# VSCard_v3_1.net
KiCad netlist of a schematic drawn in EAGLE
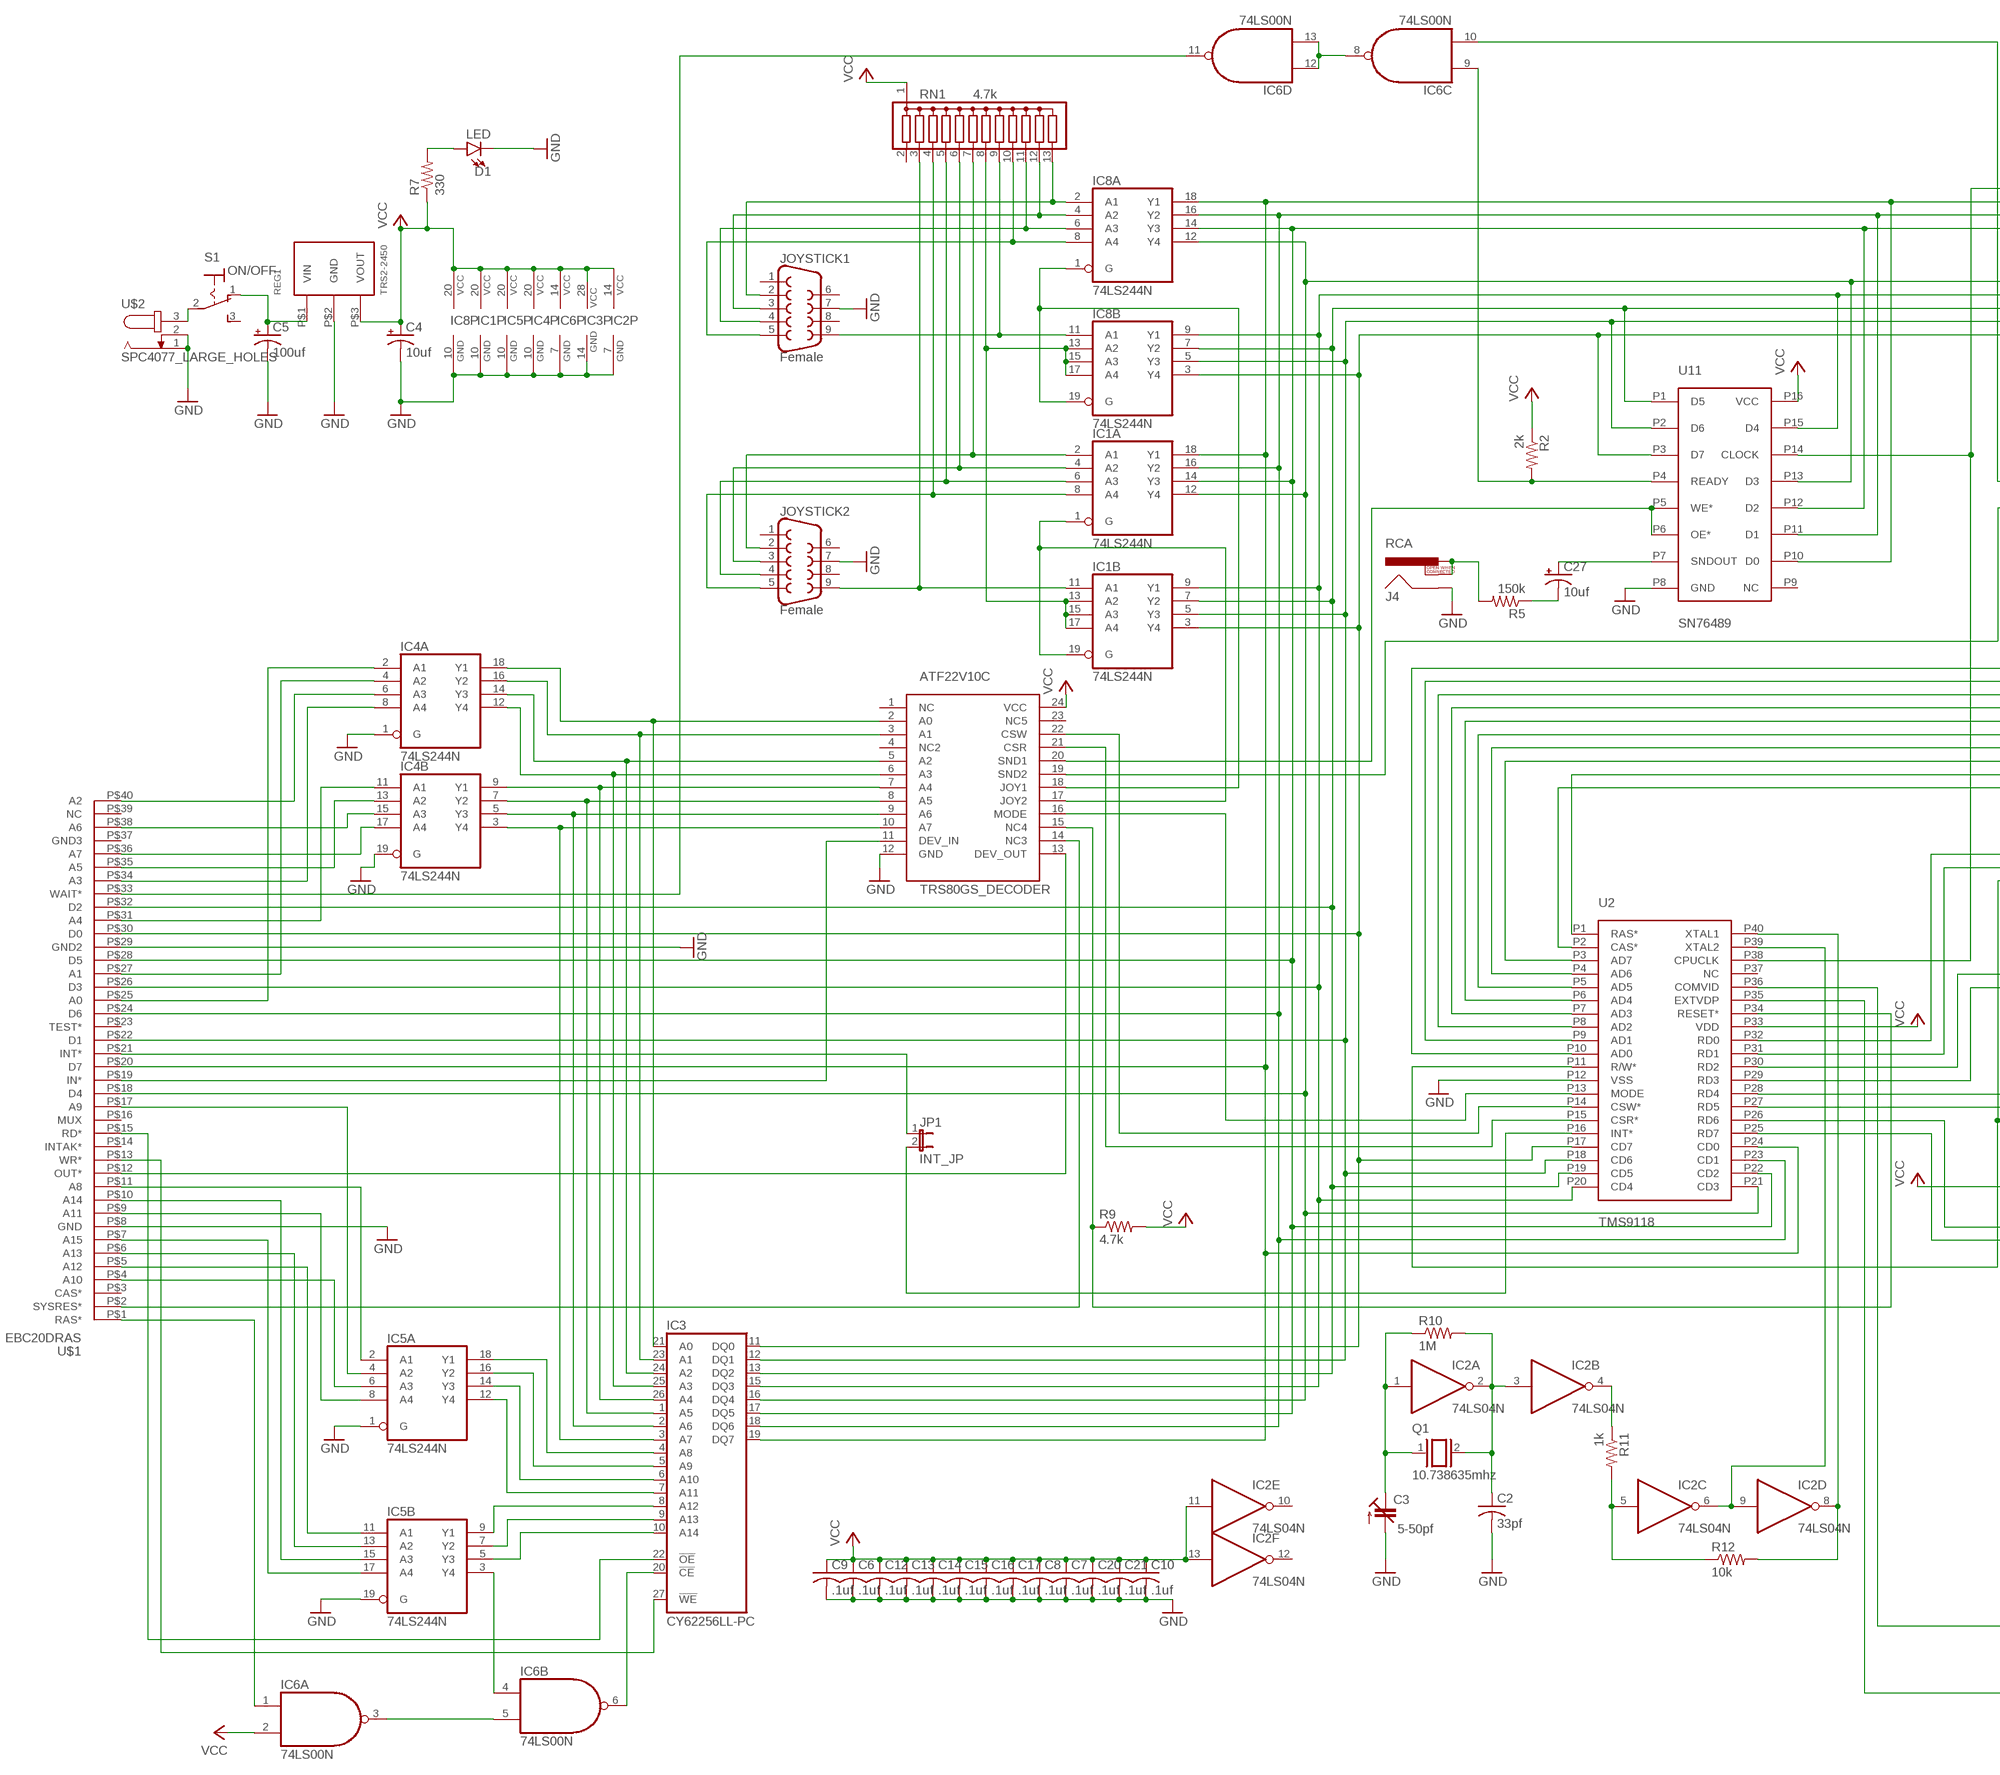
[diagram p0: schematic, sheet 1, part 1 of 2]
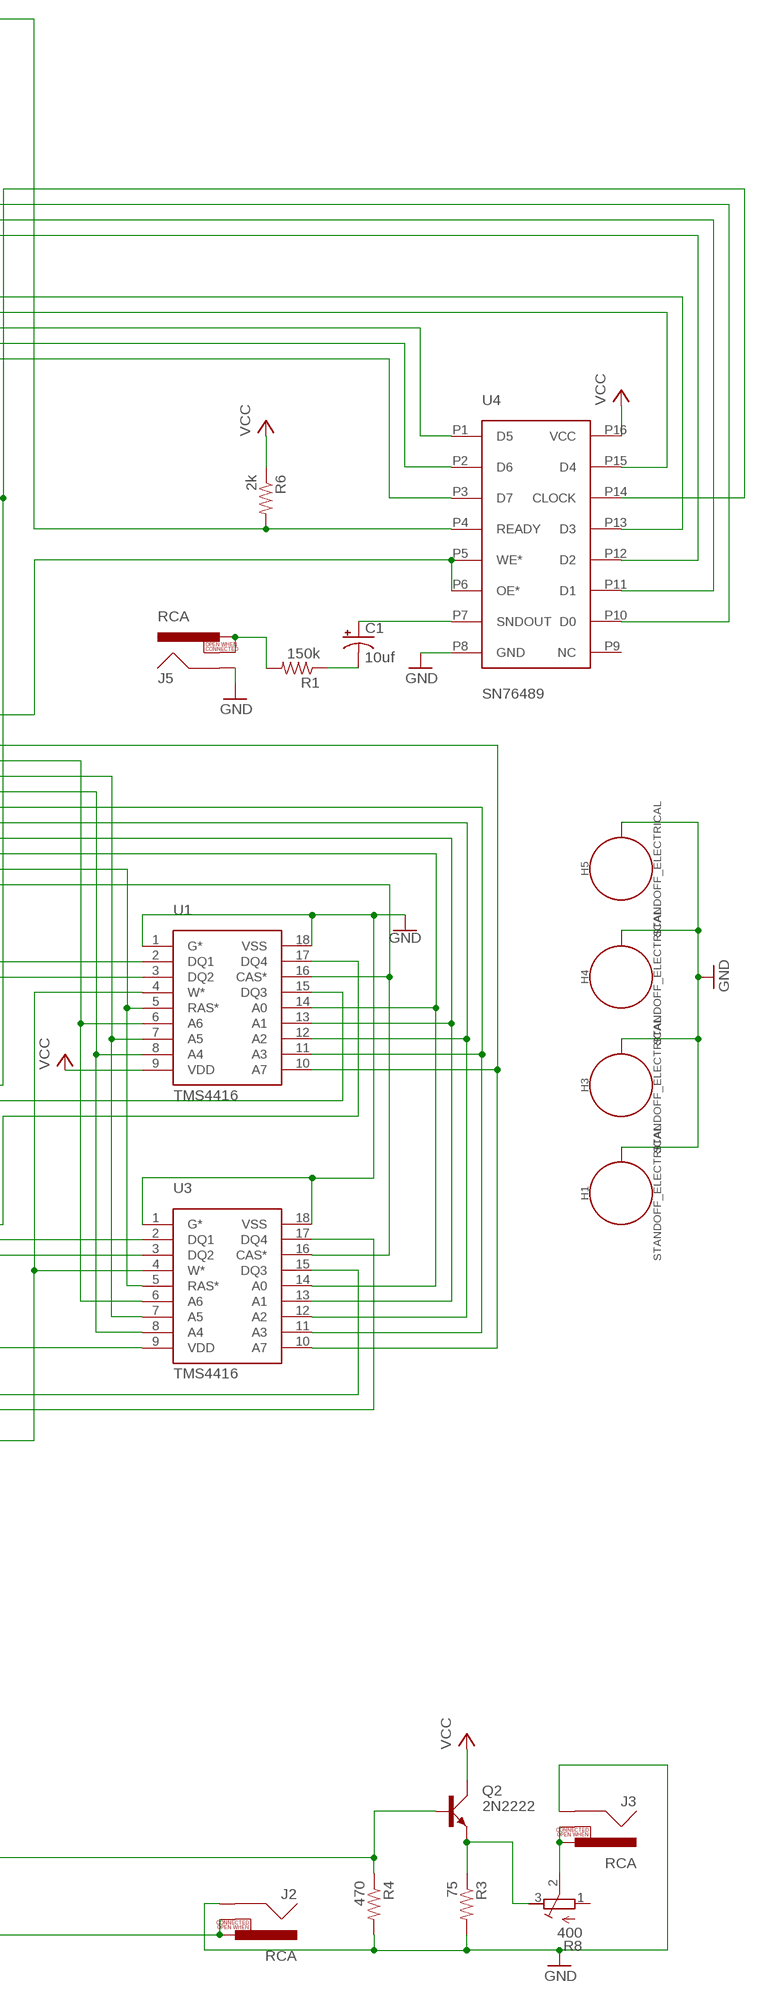
[diagram p1: schematic, sheet 1, part 2 of 2]

(export (version "E")
  (design (tool "Eeschema 10.0.6"))
  (components
    (comp (ref "ATF22V10C")
      (value "TRS80GS_DECODER")
      (footprint "eagle-import:DIP24SKI")
      (libsource (lib "eagle-import") (part "TRS80GS_DECODER"))
    )
    (comp (ref "C1")
      (value "10uf")
      (footprint "eagle-import:E2,5-6")
      (libsource (lib "eagle-import") (part "resistor_348_CPOL-USE2.5-6"))
    )
    (comp (ref "C2")
      (value "33pf")
      (footprint "eagle-import:C050-025X075")
      (libsource (lib "eagle-import") (part "C-US050-025X075"))
    )
    (comp (ref "C3")
      (value "5-50pf")
      (footprint "eagle-import:CTRIM3050.504")
      (libsource (lib "eagle-import") (part "C-TRIMM3050.504"))
    )
    (comp (ref "C4")
      (value "10uf")
      (footprint "eagle-import:E2,5-5")
      (libsource (lib "eagle-import") (part "resistor_348_CPOL-USE2.5-5"))
    )
    (comp (ref "C5")
      (value "100uf")
      (footprint "eagle-import:E3,5-10")
      (libsource (lib "eagle-import") (part "CPOL-USE3.5-10"))
    )
    (comp (ref "C6")
      (value ".1uf")
      (footprint "eagle-import:C025-025X050")
      (libsource (lib "eagle-import") (part "resistor_348_C-US025-025X050"))
    )
    (comp (ref "C7")
      (value ".1uf")
      (footprint "eagle-import:C025-025X050")
      (libsource (lib "eagle-import") (part "resistor_348_C-US025-025X050"))
    )
    (comp (ref "C8")
      (value ".1uf")
      (footprint "eagle-import:C025-025X050")
      (libsource (lib "eagle-import") (part "resistor_348_C-US025-025X050"))
    )
    (comp (ref "C9")
      (value ".1uf")
      (footprint "eagle-import:C025-025X050")
      (libsource (lib "eagle-import") (part "resistor_348_C-US025-025X050"))
    )
    (comp (ref "C10")
      (value ".1uf")
      (footprint "eagle-import:C025-025X050")
      (libsource (lib "eagle-import") (part "resistor_348_C-US025-025X050"))
    )
    (comp (ref "C12")
      (value ".1uf")
      (footprint "eagle-import:C025-025X050")
      (libsource (lib "eagle-import") (part "resistor_348_C-US025-025X050"))
    )
    (comp (ref "C13")
      (value ".1uf")
      (footprint "eagle-import:C025-025X050")
      (libsource (lib "eagle-import") (part "resistor_348_C-US025-025X050"))
    )
    (comp (ref "C14")
      (value ".1uf")
      (footprint "eagle-import:C025-025X050")
      (libsource (lib "eagle-import") (part "resistor_348_C-US025-025X050"))
    )
    (comp (ref "C15")
      (value ".1uf")
      (footprint "eagle-import:C025-025X050")
      (libsource (lib "eagle-import") (part "resistor_348_C-US025-025X050"))
    )
    (comp (ref "C16")
      (value ".1uf")
      (footprint "eagle-import:C025-025X050")
      (libsource (lib "eagle-import") (part "resistor_348_C-US025-025X050"))
    )
    (comp (ref "C17")
      (value ".1uf")
      (footprint "eagle-import:C025-025X050")
      (libsource (lib "eagle-import") (part "resistor_348_C-US025-025X050"))
    )
    (comp (ref "C20")
      (value ".1uf")
      (footprint "eagle-import:C025-025X050")
      (libsource (lib "eagle-import") (part "resistor_348_C-US025-025X050"))
    )
    (comp (ref "C21")
      (value ".1uf")
      (footprint "eagle-import:C025-025X050")
      (libsource (lib "eagle-import") (part "resistor_348_C-US025-025X050"))
    )
    (comp (ref "C27")
      (value "10uf")
      (footprint "eagle-import:E2,5-6")
      (libsource (lib "eagle-import") (part "resistor_348_CPOL-USE2.5-6"))
    )
    (comp (ref "D1")
      (value "LED")
      (footprint "eagle-import:LED_3MM")
      (libsource (lib "eagle-import") (part "LED3MM"))
    )
    (comp (ref "H1")
      (value "STANDOFF_ELECTRICAL")
      (footprint "eagle-import:STANDOFF-ELECTRICAL")
      (libsource (lib "eagle-import") (part "STANDOFF_ELECTRICAL"))
    )
    (comp (ref "H3")
      (value "STANDOFF_ELECTRICAL")
      (footprint "eagle-import:STANDOFF-ELECTRICAL")
      (libsource (lib "eagle-import") (part "STANDOFF_ELECTRICAL"))
    )
    (comp (ref "H4")
      (value "STANDOFF_ELECTRICAL")
      (footprint "eagle-import:STANDOFF-ELECTRICAL")
      (libsource (lib "eagle-import") (part "STANDOFF_ELECTRICAL"))
    )
    (comp (ref "H5")
      (value "STANDOFF_ELECTRICAL")
      (footprint "eagle-import:STANDOFF-ELECTRICAL")
      (libsource (lib "eagle-import") (part "STANDOFF_ELECTRICAL"))
    )
    (comp (ref "IC1")
      (value "74LS244N")
      (footprint "eagle-import:DIL20")
      (libsource (lib "eagle-import") (part "74244NLS"))
    )
    (comp (ref "IC2")
      (value "74LS04N")
      (footprint "eagle-import:DIL14")
      (libsource (lib "eagle-import") (part "7404NLS"))
    )
    (comp (ref "IC3")
      (value "CY62256LL-PC")
      (footprint "eagle-import:DIL28-6")
      (libsource (lib "eagle-import") (part "CY62256LL-?PC"))
    )
    (comp (ref "IC4")
      (value "74LS244N")
      (footprint "eagle-import:DIL20")
      (libsource (lib "eagle-import") (part "74244NLS"))
    )
    (comp (ref "IC5")
      (value "74LS244N")
      (footprint "eagle-import:DIL20")
      (libsource (lib "eagle-import") (part "74244NLS"))
    )
    (comp (ref "IC6")
      (value "74LS00N")
      (footprint "eagle-import:DIL14")
      (libsource (lib "eagle-import") (part "7400NLS"))
    )
    (comp (ref "IC8")
      (value "74LS244N")
      (footprint "eagle-import:DIL20")
      (libsource (lib "eagle-import") (part "74244NLS"))
    )
    (comp (ref "J2")
      (value "RCA")
      (footprint "eagle-import:RCA")
      (libsource (lib "eagle-import") (part "RCA"))
    )
    (comp (ref "J3")
      (value "RCA")
      (footprint "eagle-import:RCA")
      (libsource (lib "eagle-import") (part "RCA"))
    )
    (comp (ref "J4")
      (value "RCA")
      (footprint "eagle-import:RCA")
      (libsource (lib "eagle-import") (part "RCA"))
    )
    (comp (ref "J5")
      (value "RCA")
      (footprint "eagle-import:RCA")
      (libsource (lib "eagle-import") (part "RCA"))
    )
    (comp (ref "JOYSTICK1")
      (value "Female")
      (footprint "eagle-import:DB9")
      (libsource (lib "eagle-import") (part "DB9FEMALE"))
    )
    (comp (ref "JOYSTICK2")
      (value "Female")
      (footprint "eagle-import:DB9")
      (libsource (lib "eagle-import") (part "DB9FEMALE"))
    )
    (comp (ref "JP1")
      (value "INT_JP")
      (footprint "eagle-import:JP1")
      (libsource (lib "eagle-import") (part "JP1E"))
    )
    (comp (ref "Q1")
      (value "10.738635mhz")
      (footprint "eagle-import:QS")
      (libsource (lib "eagle-import") (part "XTAL/S"))
    )
    (comp (ref "Q2")
      (value "2N2222")
      (footprint "eagle-import:TO18A")
      (libsource (lib "eagle-import") (part "2N2222"))
    )
    (comp (ref "R1")
      (value "150k")
      (footprint "eagle-import:0207_2V")
      (libsource (lib "eagle-import") (part "resistor_348_R-US_0207/2V"))
    )
    (comp (ref "R2")
      (value "2k")
      (footprint "eagle-import:0207_2V")
      (libsource (lib "eagle-import") (part "resistor_348_R-US_0207/2V"))
    )
    (comp (ref "R3")
      (value "75")
      (footprint "eagle-import:0207_2V")
      (libsource (lib "eagle-import") (part "resistor_348_R-US_0207/2V"))
    )
    (comp (ref "R4")
      (value "470")
      (footprint "eagle-import:0207_2V")
      (libsource (lib "eagle-import") (part "resistor_348_R-US_0207/2V"))
    )
    (comp (ref "R5")
      (value "150k")
      (footprint "eagle-import:0207_2V")
      (libsource (lib "eagle-import") (part "resistor_348_R-US_0207/2V"))
    )
    (comp (ref "R6")
      (value "2k")
      (footprint "eagle-import:0207_2V")
      (libsource (lib "eagle-import") (part "resistor_348_R-US_0207/2V"))
    )
    (comp (ref "R7")
      (value "330")
      (footprint "eagle-import:0309V")
      (libsource (lib "eagle-import") (part "resistor_348_R-US_0309/V"))
    )
    (comp (ref "R8")
      (value "400")
      (footprint "eagle-import:RTRIM64W")
      (libsource (lib "eagle-import") (part "R-TRIMM64W"))
    )
    (comp (ref "R9")
      (value "4.7k")
      (footprint "eagle-import:0207_2V")
      (libsource (lib "eagle-import") (part "resistor_348_R-US_0207/2V"))
    )
    (comp (ref "R10")
      (value "1M")
      (footprint "eagle-import:0204V")
      (libsource (lib "eagle-import") (part "R-US_0204/2V"))
    )
    (comp (ref "R11")
      (value "1k")
      (footprint "eagle-import:0204V")
      (libsource (lib "eagle-import") (part "R-US_0204/2V"))
    )
    (comp (ref "R12")
      (value "10k")
      (footprint "eagle-import:0204V")
      (libsource (lib "eagle-import") (part "R-US_0204/2V"))
    )
    (comp (ref "REG1")
      (value "TRS2-2450")
      (footprint "eagle-import:TRACON_REG")
      (libsource (lib "eagle-import") (part "TRS2-2450"))
    )
    (comp (ref "RN1")
      (value "4.7k")
      (footprint "eagle-import:SIL13")
      (libsource (lib "eagle-import") (part "G12R"))
    )
    (comp (ref "S1")
      (value "ON/OFF")
      (footprint "eagle-import:320-916")
      (libsource (lib "eagle-import") (part "320-916"))
    )
    (comp (ref "U$1")
      (value "EBC20DRAS")
      (footprint "eagle-import:EBC20DRAS")
      (libsource (lib "eagle-import") (part "EBC20DRAS"))
    )
    (comp (ref "U$2")
      (value "SPC4077_LARGE_HOLES")
      (footprint "eagle-import:SPC4077")
      (libsource (lib "eagle-import") (part "SPC4077_LARGE_HOLES"))
    )
    (comp (ref "U1")
      (value "TMS4416")
      (footprint "eagle-import:DIP18")
      (libsource (lib "eagle-import") (part "TMS4416"))
    )
    (comp (ref "U2")
      (value "TMS9118")
      (footprint "eagle-import:DIP40_MCU")
      (libsource (lib "eagle-import") (part "TMS9118"))
    )
    (comp (ref "U3")
      (value "TMS4416")
      (footprint "eagle-import:DIP18")
      (libsource (lib "eagle-import") (part "TMS4416"))
    )
    (comp (ref "U4")
      (value "SN76489")
      (footprint "eagle-import:DIP16")
      (libsource (lib "eagle-import") (part "SN76489"))
    )
    (comp (ref "U11")
      (value "SN76489")
      (footprint "eagle-import:DIP16")
      (libsource (lib "eagle-import") (part "SN76489"))
    )
  )
  (nets
    (net (code "1") (name "GND") (class "Default")
      (node (ref "ATF22V10C") (pin "12") (pinfunction "GND_12") (pintype "bidirectional"))
      (node (ref "C10") (pin "2") (pinfunction "2_2") (pintype "passive"))
      (node (ref "C12") (pin "2") (pinfunction "2_2") (pintype "passive"))
      (node (ref "C13") (pin "2") (pinfunction "2_2") (pintype "passive"))
      (node (ref "C14") (pin "2") (pinfunction "2_2") (pintype "passive"))
      (node (ref "C15") (pin "2") (pinfunction "2_2") (pintype "passive"))
      (node (ref "C16") (pin "2") (pinfunction "2_2") (pintype "passive"))
      (node (ref "C17") (pin "2") (pinfunction "2_2") (pintype "passive"))
      (node (ref "C2") (pin "2") (pinfunction "2_2") (pintype "passive"))
      (node (ref "C20") (pin "2") (pinfunction "2_2") (pintype "passive"))
      (node (ref "C21") (pin "2") (pinfunction "2_2") (pintype "passive"))
      (node (ref "C3") (pin "2") (pinfunction "A_2") (pintype "passive"))
      (node (ref "C4") (pin "-") (pinfunction "-_-") (pintype "passive"))
      (node (ref "C5") (pin "-") (pinfunction "-_-") (pintype "passive"))
      (node (ref "C6") (pin "2") (pinfunction "2_2") (pintype "passive"))
      (node (ref "C7") (pin "2") (pinfunction "2_2") (pintype "passive"))
      (node (ref "C8") (pin "2") (pinfunction "2_2") (pintype "passive"))
      (node (ref "C9") (pin "2") (pinfunction "2_2") (pintype "passive"))
      (node (ref "D1") (pin "K") (pinfunction "C_K") (pintype "passive"))
      (node (ref "H1") (pin "P1") (pinfunction "P$1_P1") (pintype "bidirectional"))
      (node (ref "H3") (pin "P1") (pinfunction "P$1_P1") (pintype "bidirectional"))
      (node (ref "H4") (pin "P1") (pinfunction "P$1_P1") (pintype "bidirectional"))
      (node (ref "H5") (pin "P1") (pinfunction "P$1_P1") (pintype "bidirectional"))
      (node (ref "IC1") (pin "10") (pinfunction "GND_10") (pintype "power_in"))
      (node (ref "IC2") (pin "7") (pinfunction "GND_7") (pintype "power_in"))
      (node (ref "IC3") (pin "14") (pinfunction "GND_14") (pintype "power_in"))
      (node (ref "IC4") (pin "1") (pinfunction "G_1") (pintype "input"))
      (node (ref "IC4") (pin "10") (pinfunction "GND_10") (pintype "power_in"))
      (node (ref "IC4") (pin "19") (pinfunction "G_19") (pintype "input"))
      (node (ref "IC5") (pin "1") (pinfunction "G_1") (pintype "input"))
      (node (ref "IC5") (pin "10") (pinfunction "GND_10") (pintype "power_in"))
      (node (ref "IC5") (pin "19") (pinfunction "G_19") (pintype "input"))
      (node (ref "IC6") (pin "7") (pinfunction "GND_7") (pintype "power_in"))
      (node (ref "IC8") (pin "10") (pinfunction "GND_10") (pintype "power_in"))
      (node (ref "J2") (pin "SHELL") (pinfunction "SHELL_SHELL") (pintype "bidirectional"))
      (node (ref "J3") (pin "SHELL") (pinfunction "SHELL_SHELL") (pintype "bidirectional"))
      (node (ref "J4") (pin "SHELL") (pinfunction "SHELL_SHELL") (pintype "bidirectional"))
      (node (ref "J5") (pin "SHELL") (pinfunction "SHELL_SHELL") (pintype "bidirectional"))
      (node (ref "JOYSTICK1") (pin "7") (pinfunction "7_7") (pintype "passive"))
      (node (ref "JOYSTICK2") (pin "7") (pinfunction "7_7") (pintype "passive"))
      (node (ref "R3") (pin "2") (pinfunction "2_2") (pintype "passive"))
      (node (ref "R4") (pin "2") (pinfunction "2_2") (pintype "passive"))
      (node (ref "REG1") (pin "P$2") (pinfunction "GND_P$2") (pintype "bidirectional"))
      (node (ref "U$1") (pin "P$29") (pinfunction "GND2_P$29") (pintype "bidirectional"))
      (node (ref "U$1") (pin "P$8") (pinfunction "GND_P$8") (pintype "bidirectional"))
      (node (ref "U$2") (pin "1") (pinfunction "1_1") (pintype "passive"))
      (node (ref "U$2") (pin "2") (pinfunction "2_2") (pintype "passive"))
      (node (ref "U1") (pin "1") (pinfunction "G*_1") (pintype "bidirectional"))
      (node (ref "U1") (pin "18") (pinfunction "VSS_18") (pintype "bidirectional"))
      (node (ref "U11") (pin "P8") (pinfunction "GND_P8") (pintype "bidirectional"))
      (node (ref "U2") (pin "P12") (pinfunction "VSS_P12") (pintype "bidirectional"))
      (node (ref "U3") (pin "1") (pinfunction "G*_1") (pintype "bidirectional"))
      (node (ref "U3") (pin "18") (pinfunction "VSS_18") (pintype "bidirectional"))
      (node (ref "U4") (pin "P8") (pinfunction "GND_P8") (pintype "bidirectional"))
    )
    (net (code "2") (name "Net-(ATF22V10C-A0)") (class "Default")
      (node (ref "ATF22V10C") (pin "2") (pinfunction "A0_2") (pintype "bidirectional"))
      (node (ref "IC3") (pin "21") (pinfunction "A0_21") (pintype "input"))
      (node (ref "IC4") (pin "18") (pinfunction "Y1_18") (pintype "tri_state"))
    )
    (net (code "3") (name "Net-(ATF22V10C-A1)") (class "Default")
      (node (ref "ATF22V10C") (pin "3") (pinfunction "A1_3") (pintype "bidirectional"))
      (node (ref "IC3") (pin "23") (pinfunction "A1_23") (pintype "input"))
      (node (ref "IC4") (pin "16") (pinfunction "Y2_16") (pintype "tri_state"))
    )
    (net (code "4") (name "Net-(ATF22V10C-A2)") (class "Default")
      (node (ref "ATF22V10C") (pin "5") (pinfunction "A2_5") (pintype "bidirectional"))
      (node (ref "IC3") (pin "24") (pinfunction "A2_24") (pintype "input"))
      (node (ref "IC4") (pin "14") (pinfunction "Y3_14") (pintype "tri_state"))
    )
    (net (code "5") (name "Net-(ATF22V10C-A3)") (class "Default")
      (node (ref "ATF22V10C") (pin "6") (pinfunction "A3_6") (pintype "bidirectional"))
      (node (ref "IC3") (pin "25") (pinfunction "A3_25") (pintype "input"))
      (node (ref "IC4") (pin "12") (pinfunction "Y4_12") (pintype "tri_state"))
    )
    (net (code "6") (name "Net-(ATF22V10C-A4)") (class "Default")
      (node (ref "ATF22V10C") (pin "7") (pinfunction "A4_7") (pintype "bidirectional"))
      (node (ref "IC3") (pin "26") (pinfunction "A4_26") (pintype "input"))
      (node (ref "IC4") (pin "9") (pinfunction "Y1_9") (pintype "tri_state"))
    )
    (net (code "7") (name "Net-(ATF22V10C-A5)") (class "Default")
      (node (ref "ATF22V10C") (pin "8") (pinfunction "A5_8") (pintype "bidirectional"))
      (node (ref "IC3") (pin "1") (pinfunction "A5_1") (pintype "input"))
      (node (ref "IC4") (pin "7") (pinfunction "Y2_7") (pintype "tri_state"))
    )
    (net (code "8") (name "Net-(ATF22V10C-A6)") (class "Default")
      (node (ref "ATF22V10C") (pin "9") (pinfunction "A6_9") (pintype "bidirectional"))
      (node (ref "IC3") (pin "2") (pinfunction "A6_2") (pintype "input"))
      (node (ref "IC4") (pin "5") (pinfunction "Y3_5") (pintype "tri_state"))
    )
    (net (code "9") (name "Net-(ATF22V10C-A7)") (class "Default")
      (node (ref "ATF22V10C") (pin "10") (pinfunction "A7_10") (pintype "bidirectional"))
      (node (ref "IC3") (pin "3") (pinfunction "A7_3") (pintype "input"))
      (node (ref "IC4") (pin "3") (pinfunction "Y4_3") (pintype "tri_state"))
    )
    (net (code "10") (name "Net-(ATF22V10C-CSR)") (class "Default")
      (node (ref "ATF22V10C") (pin "21") (pinfunction "CSR_21") (pintype "bidirectional"))
      (node (ref "U2") (pin "P15") (pinfunction "CSR*_P15") (pintype "bidirectional"))
    )
    (net (code "11") (name "Net-(ATF22V10C-CSW)") (class "Default")
      (node (ref "ATF22V10C") (pin "22") (pinfunction "CSW_22") (pintype "bidirectional"))
      (node (ref "U2") (pin "P14") (pinfunction "CSW*_P14") (pintype "bidirectional"))
    )
    (net (code "12") (name "Net-(ATF22V10C-DEV_IN)") (class "Default")
      (node (ref "ATF22V10C") (pin "11") (pinfunction "DEV_IN_11") (pintype "bidirectional"))
      (node (ref "U$1") (pin "P$19") (pinfunction "IN*_P$19") (pintype "bidirectional"))
    )
    (net (code "13") (name "Net-(ATF22V10C-DEV_OUT)") (class "Default")
      (node (ref "ATF22V10C") (pin "13") (pinfunction "DEV_OUT_13") (pintype "bidirectional"))
      (node (ref "U$1") (pin "P$12") (pinfunction "OUT*_P$12") (pintype "bidirectional"))
    )
    (net (code "14") (name "Net-(ATF22V10C-JOY1)") (class "Default")
      (node (ref "ATF22V10C") (pin "18") (pinfunction "JOY1_18") (pintype "bidirectional"))
      (node (ref "IC8") (pin "1") (pinfunction "G_1") (pintype "input"))
      (node (ref "IC8") (pin "19") (pinfunction "G_19") (pintype "input"))
    )
    (net (code "15") (name "Net-(ATF22V10C-JOY2)") (class "Default")
      (node (ref "ATF22V10C") (pin "17") (pinfunction "JOY2_17") (pintype "bidirectional"))
      (node (ref "IC1") (pin "1") (pinfunction "G_1") (pintype "input"))
      (node (ref "IC1") (pin "19") (pinfunction "G_19") (pintype "input"))
    )
    (net (code "16") (name "Net-(ATF22V10C-MODE)") (class "Default")
      (node (ref "ATF22V10C") (pin "16") (pinfunction "MODE_16") (pintype "bidirectional"))
      (node (ref "U2") (pin "P13") (pinfunction "MODE_P13") (pintype "bidirectional"))
    )
    (net (code "17") (name "Net-(ATF22V10C-NC3)") (class "Default")
      (node (ref "ATF22V10C") (pin "14") (pinfunction "NC3_14") (pintype "bidirectional"))
      (node (ref "U$1") (pin "P$2") (pinfunction "SYSRES*_P$2") (pintype "bidirectional"))
    )
    (net (code "18") (name "Net-(ATF22V10C-NC4)") (class "Default")
      (node (ref "ATF22V10C") (pin "15") (pinfunction "NC4_15") (pintype "bidirectional"))
      (node (ref "R9") (pin "1") (pinfunction "1_1") (pintype "passive"))
      (node (ref "U2") (pin "P34") (pinfunction "RESET*_P34") (pintype "bidirectional"))
    )
    (net (code "19") (name "Net-(ATF22V10C-SND1)") (class "Default")
      (node (ref "ATF22V10C") (pin "20") (pinfunction "SND1_20") (pintype "bidirectional"))
      (node (ref "U11") (pin "P5") (pinfunction "WE*_P5") (pintype "bidirectional"))
      (node (ref "U11") (pin "P6") (pinfunction "OE*_P6") (pintype "bidirectional"))
    )
    (net (code "20") (name "Net-(ATF22V10C-SND2)") (class "Default")
      (node (ref "ATF22V10C") (pin "19") (pinfunction "SND2_19") (pintype "bidirectional"))
      (node (ref "U4") (pin "P5") (pinfunction "WE*_P5") (pintype "bidirectional"))
      (node (ref "U4") (pin "P6") (pinfunction "OE*_P6") (pintype "bidirectional"))
    )
    (net (code "21") (name "Net-(C1-Pad-)") (class "Default")
      (node (ref "C1") (pin "-") (pinfunction "-_-") (pintype "passive"))
      (node (ref "R1") (pin "1") (pinfunction "1_1") (pintype "passive"))
    )
    (net (code "22") (name "Net-(C3-E)") (class "Default")
      (node (ref "C3") (pin "1") (pinfunction "E_1") (pintype "passive"))
      (node (ref "IC2") (pin "1") (pinfunction "I_1") (pintype "input"))
      (node (ref "Q1") (pin "1") (pinfunction "1_1") (pintype "passive"))
      (node (ref "R10") (pin "1") (pinfunction "1_1") (pintype "passive"))
    )
    (net (code "23") (name "Net-(C27-Pad-)") (class "Default")
      (node (ref "C27") (pin "-") (pinfunction "-_-") (pintype "passive"))
      (node (ref "R5") (pin "1") (pinfunction "1_1") (pintype "passive"))
    )
    (net (code "24") (name "Net-(D1-PadA)") (class "Default")
      (node (ref "D1") (pin "A") (pinfunction "A_A") (pintype "passive"))
      (node (ref "R7") (pin "2") (pinfunction "2_2") (pintype "passive"))
    )
    (net (code "25") (name "Net-(IC1A-A1)") (class "Default")
      (node (ref "IC1") (pin "2") (pinfunction "A1_2") (pintype "input"))
      (node (ref "JOYSTICK2") (pin "2") (pinfunction "2_2") (pintype "passive"))
      (node (ref "RN1") (pin "7") (pinfunction "7_7") (pintype "passive"))
    )
    (net (code "26") (name "Net-(IC1A-A2)") (class "Default")
      (node (ref "IC1") (pin "4") (pinfunction "A2_4") (pintype "input"))
      (node (ref "JOYSTICK2") (pin "3") (pinfunction "3_3") (pintype "passive"))
      (node (ref "RN1") (pin "6") (pinfunction "6_6") (pintype "passive"))
    )
    (net (code "27") (name "Net-(IC1A-A3)") (class "Default")
      (node (ref "IC1") (pin "6") (pinfunction "A3_6") (pintype "input"))
      (node (ref "JOYSTICK2") (pin "4") (pinfunction "4_4") (pintype "passive"))
      (node (ref "RN1") (pin "5") (pinfunction "5_5") (pintype "passive"))
    )
    (net (code "28") (name "Net-(IC1A-A4)") (class "Default")
      (node (ref "IC1") (pin "8") (pinfunction "A4_8") (pintype "input"))
      (node (ref "JOYSTICK2") (pin "5") (pinfunction "5_5") (pintype "passive"))
      (node (ref "RN1") (pin "4") (pinfunction "4_4") (pintype "passive"))
    )
    (net (code "29") (name "Net-(IC1A-Y1)") (class "Default")
      (node (ref "IC1") (pin "18") (pinfunction "Y1_18") (pintype "tri_state"))
      (node (ref "IC3") (pin "19") (pinfunction "DQ7_19") (pintype "bidirectional"))
      (node (ref "IC8") (pin "18") (pinfunction "Y1_18") (pintype "tri_state"))
      (node (ref "U$1") (pin "P$20") (pinfunction "D7_P$20") (pintype "bidirectional"))
      (node (ref "U11") (pin "P10") (pinfunction "D0_P10") (pintype "bidirectional"))
      (node (ref "U2") (pin "P24") (pinfunction "CD0_P24") (pintype "bidirectional"))
      (node (ref "U4") (pin "P10") (pinfunction "D0_P10") (pintype "bidirectional"))
    )
    (net (code "30") (name "Net-(IC1A-Y2)") (class "Default")
      (node (ref "IC1") (pin "16") (pinfunction "Y2_16") (pintype "tri_state"))
      (node (ref "IC3") (pin "18") (pinfunction "DQ6_18") (pintype "bidirectional"))
      (node (ref "IC8") (pin "16") (pinfunction "Y2_16") (pintype "tri_state"))
      (node (ref "U$1") (pin "P$24") (pinfunction "D6_P$24") (pintype "bidirectional"))
      (node (ref "U11") (pin "P11") (pinfunction "D1_P11") (pintype "bidirectional"))
      (node (ref "U2") (pin "P23") (pinfunction "CD1_P23") (pintype "bidirectional"))
      (node (ref "U4") (pin "P11") (pinfunction "D1_P11") (pintype "bidirectional"))
    )
    (net (code "31") (name "Net-(IC1A-Y3)") (class "Default")
      (node (ref "IC1") (pin "14") (pinfunction "Y3_14") (pintype "tri_state"))
      (node (ref "IC3") (pin "17") (pinfunction "DQ5_17") (pintype "bidirectional"))
      (node (ref "IC8") (pin "14") (pinfunction "Y3_14") (pintype "tri_state"))
      (node (ref "U$1") (pin "P$28") (pinfunction "D5_P$28") (pintype "bidirectional"))
      (node (ref "U11") (pin "P12") (pinfunction "D2_P12") (pintype "bidirectional"))
      (node (ref "U2") (pin "P22") (pinfunction "CD2_P22") (pintype "bidirectional"))
      (node (ref "U4") (pin "P12") (pinfunction "D2_P12") (pintype "bidirectional"))
    )
    (net (code "32") (name "Net-(IC1A-Y4)") (class "Default")
      (node (ref "IC1") (pin "12") (pinfunction "Y4_12") (pintype "tri_state"))
      (node (ref "IC3") (pin "16") (pinfunction "DQ4_16") (pintype "bidirectional"))
      (node (ref "IC8") (pin "12") (pinfunction "Y4_12") (pintype "tri_state"))
      (node (ref "U$1") (pin "P$18") (pinfunction "D4_P$18") (pintype "bidirectional"))
      (node (ref "U11") (pin "P13") (pinfunction "D3_P13") (pintype "bidirectional"))
      (node (ref "U2") (pin "P21") (pinfunction "CD3_P21") (pintype "bidirectional"))
      (node (ref "U4") (pin "P13") (pinfunction "D3_P13") (pintype "bidirectional"))
    )
    (net (code "33") (name "Net-(IC1B-A1)") (class "Default")
      (node (ref "IC1") (pin "11") (pinfunction "A1_11") (pintype "input"))
      (node (ref "JOYSTICK2") (pin "9") (pinfunction "9_9") (pintype "passive"))
      (node (ref "RN1") (pin "3") (pinfunction "3_3") (pintype "passive"))
    )
    (net (code "34") (name "Net-(IC1B-A2)") (class "Default")
      (node (ref "IC1") (pin "13") (pinfunction "A2_13") (pintype "input"))
      (node (ref "IC1") (pin "15") (pinfunction "A3_15") (pintype "input"))
      (node (ref "IC1") (pin "17") (pinfunction "A4_17") (pintype "input"))
      (node (ref "IC8") (pin "13") (pinfunction "A2_13") (pintype "input"))
      (node (ref "IC8") (pin "15") (pinfunction "A3_15") (pintype "input"))
      (node (ref "IC8") (pin "17") (pinfunction "A4_17") (pintype "input"))
      (node (ref "RN1") (pin "8") (pinfunction "8_8") (pintype "passive"))
    )
    (net (code "35") (name "Net-(IC1B-Y1)") (class "Default")
      (node (ref "IC1") (pin "9") (pinfunction "Y1_9") (pintype "tri_state"))
      (node (ref "IC3") (pin "15") (pinfunction "DQ3_15") (pintype "bidirectional"))
      (node (ref "IC8") (pin "9") (pinfunction "Y1_9") (pintype "tri_state"))
      (node (ref "U$1") (pin "P$26") (pinfunction "D3_P$26") (pintype "bidirectional"))
      (node (ref "U11") (pin "P15") (pinfunction "D4_P15") (pintype "bidirectional"))
      (node (ref "U2") (pin "P20") (pinfunction "CD4_P20") (pintype "bidirectional"))
      (node (ref "U4") (pin "P15") (pinfunction "D4_P15") (pintype "bidirectional"))
    )
    (net (code "36") (name "Net-(IC1B-Y2)") (class "Default")
      (node (ref "IC1") (pin "7") (pinfunction "Y2_7") (pintype "tri_state"))
      (node (ref "IC3") (pin "13") (pinfunction "DQ2_13") (pintype "bidirectional"))
      (node (ref "IC8") (pin "7") (pinfunction "Y2_7") (pintype "tri_state"))
      (node (ref "U$1") (pin "P$32") (pinfunction "D2_P$32") (pintype "bidirectional"))
      (node (ref "U11") (pin "P1") (pinfunction "D5_P1") (pintype "bidirectional"))
      (node (ref "U2") (pin "P19") (pinfunction "CD5_P19") (pintype "bidirectional"))
      (node (ref "U4") (pin "P1") (pinfunction "D5_P1") (pintype "bidirectional"))
    )
    (net (code "37") (name "Net-(IC1B-Y3)") (class "Default")
      (node (ref "IC1") (pin "5") (pinfunction "Y3_5") (pintype "tri_state"))
      (node (ref "IC3") (pin "12") (pinfunction "DQ1_12") (pintype "bidirectional"))
      (node (ref "IC8") (pin "5") (pinfunction "Y3_5") (pintype "tri_state"))
      (node (ref "U$1") (pin "P$22") (pinfunction "D1_P$22") (pintype "bidirectional"))
      (node (ref "U11") (pin "P2") (pinfunction "D6_P2") (pintype "bidirectional"))
      (node (ref "U2") (pin "P18") (pinfunction "CD6_P18") (pintype "bidirectional"))
      (node (ref "U4") (pin "P2") (pinfunction "D6_P2") (pintype "bidirectional"))
    )
    (net (code "38") (name "Net-(IC1B-Y4)") (class "Default")
      (node (ref "IC1") (pin "3") (pinfunction "Y4_3") (pintype "tri_state"))
      (node (ref "IC3") (pin "11") (pinfunction "DQ0_11") (pintype "bidirectional"))
      (node (ref "IC8") (pin "3") (pinfunction "Y4_3") (pintype "tri_state"))
      (node (ref "U$1") (pin "P$30") (pinfunction "D0_P$30") (pintype "bidirectional"))
      (node (ref "U11") (pin "P3") (pinfunction "D7_P3") (pintype "bidirectional"))
      (node (ref "U2") (pin "P17") (pinfunction "CD7_P17") (pintype "bidirectional"))
      (node (ref "U4") (pin "P3") (pinfunction "D7_P3") (pintype "bidirectional"))
    )
    (net (code "39") (name "Net-(IC2A-O)") (class "Default")
      (node (ref "C2") (pin "1") (pinfunction "1_1") (pintype "passive"))
      (node (ref "IC2") (pin "2") (pinfunction "O_2") (pintype "output"))
      (node (ref "IC2") (pin "3") (pinfunction "I_3") (pintype "input"))
      (node (ref "Q1") (pin "2") (pinfunction "2_2") (pintype "passive"))
      (node (ref "R10") (pin "2") (pinfunction "2_2") (pintype "passive"))
    )
    (net (code "40") (name "Net-(IC2B-O)") (class "Default")
      (node (ref "IC2") (pin "4") (pinfunction "O_4") (pintype "output"))
      (node (ref "R11") (pin "1") (pinfunction "1_1") (pintype "passive"))
    )
    (net (code "41") (name "Net-(IC2C-I)") (class "Default")
      (node (ref "IC2") (pin "5") (pinfunction "I_5") (pintype "input"))
      (node (ref "R11") (pin "2") (pinfunction "2_2") (pintype "passive"))
      (node (ref "R12") (pin "1") (pinfunction "1_1") (pintype "passive"))
    )
    (net (code "42") (name "Net-(IC2C-O)") (class "Default")
      (node (ref "IC2") (pin "6") (pinfunction "O_6") (pintype "output"))
      (node (ref "IC2") (pin "9") (pinfunction "I_9") (pintype "input"))
      (node (ref "U2") (pin "P39") (pinfunction "XTAL2_P39") (pintype "bidirectional"))
    )
    (net (code "43") (name "Net-(IC2D-O)") (class "Default")
      (node (ref "IC2") (pin "8") (pinfunction "O_8") (pintype "output"))
      (node (ref "R12") (pin "2") (pinfunction "2_2") (pintype "passive"))
      (node (ref "U2") (pin "P40") (pinfunction "XTAL1_P40") (pintype "bidirectional"))
    )
    (net (code "44") (name "Net-(IC3A-A8)") (class "Default")
      (node (ref "IC3") (pin "4") (pinfunction "A8_4") (pintype "input"))
      (node (ref "IC5") (pin "18") (pinfunction "Y1_18") (pintype "tri_state"))
    )
    (net (code "45") (name "Net-(IC3A-A9)") (class "Default")
      (node (ref "IC3") (pin "5") (pinfunction "A9_5") (pintype "input"))
      (node (ref "IC5") (pin "16") (pinfunction "Y2_16") (pintype "tri_state"))
    )
    (net (code "46") (name "Net-(IC3A-A10)") (class "Default")
      (node (ref "IC3") (pin "6") (pinfunction "A10_6") (pintype "input"))
      (node (ref "IC5") (pin "14") (pinfunction "Y3_14") (pintype "tri_state"))
    )
    (net (code "47") (name "Net-(IC3A-A11)") (class "Default")
      (node (ref "IC3") (pin "7") (pinfunction "A11_7") (pintype "input"))
      (node (ref "IC5") (pin "12") (pinfunction "Y4_12") (pintype "tri_state"))
    )
    (net (code "48") (name "Net-(IC3A-A12)") (class "Default")
      (node (ref "IC3") (pin "8") (pinfunction "A12_8") (pintype "input"))
      (node (ref "IC5") (pin "9") (pinfunction "Y1_9") (pintype "tri_state"))
    )
    (net (code "49") (name "Net-(IC3A-A13)") (class "Default")
      (node (ref "IC3") (pin "9") (pinfunction "A13_9") (pintype "input"))
      (node (ref "IC5") (pin "7") (pinfunction "Y2_7") (pintype "tri_state"))
    )
    (net (code "50") (name "Net-(IC3A-A14)") (class "Default")
      (node (ref "IC3") (pin "10") (pinfunction "A14_10") (pintype "input"))
      (node (ref "IC5") (pin "5") (pinfunction "Y3_5") (pintype "tri_state"))
    )
    (net (code "51") (name "Net-(IC3A-~{CE})") (class "Default")
      (node (ref "IC3") (pin "20") (pinfunction "~{CE}_20") (pintype "input"))
      (node (ref "IC6") (pin "6") (pinfunction "O_6") (pintype "output"))
    )
    (net (code "52") (name "Net-(IC3A-~{OE})") (class "Default")
      (node (ref "IC3") (pin "22") (pinfunction "~{OE}_22") (pintype "input"))
      (node (ref "U$1") (pin "P$15") (pinfunction "RD*_P$15") (pintype "bidirectional"))
    )
    (net (code "53") (name "Net-(IC3A-~{WE})") (class "Default")
      (node (ref "IC3") (pin "27") (pinfunction "~{WE}_27") (pintype "input"))
      (node (ref "U$1") (pin "P$13") (pinfunction "WR*_P$13") (pintype "bidirectional"))
    )
    (net (code "54") (name "Net-(IC4A-A1)") (class "Default")
      (node (ref "IC4") (pin "2") (pinfunction "A1_2") (pintype "input"))
      (node (ref "U$1") (pin "P$25") (pinfunction "A0_P$25") (pintype "bidirectional"))
    )
    (net (code "55") (name "Net-(IC4A-A2)") (class "Default")
      (node (ref "IC4") (pin "4") (pinfunction "A2_4") (pintype "input"))
      (node (ref "U$1") (pin "P$27") (pinfunction "A1_P$27") (pintype "bidirectional"))
    )
    (net (code "56") (name "Net-(IC4A-A3)") (class "Default")
      (node (ref "IC4") (pin "6") (pinfunction "A3_6") (pintype "input"))
      (node (ref "U$1") (pin "P$40") (pinfunction "A2_P$40") (pintype "bidirectional"))
    )
    (net (code "57") (name "Net-(IC4A-A4)") (class "Default")
      (node (ref "IC4") (pin "8") (pinfunction "A4_8") (pintype "input"))
      (node (ref "U$1") (pin "P$34") (pinfunction "A3_P$34") (pintype "bidirectional"))
    )
    (net (code "58") (name "Net-(IC4B-A1)") (class "Default")
      (node (ref "IC4") (pin "11") (pinfunction "A1_11") (pintype "input"))
      (node (ref "U$1") (pin "P$31") (pinfunction "A4_P$31") (pintype "bidirectional"))
    )
    (net (code "59") (name "Net-(IC4B-A2)") (class "Default")
      (node (ref "IC4") (pin "13") (pinfunction "A2_13") (pintype "input"))
      (node (ref "U$1") (pin "P$35") (pinfunction "A5_P$35") (pintype "bidirectional"))
    )
    (net (code "60") (name "Net-(IC4B-A3)") (class "Default")
      (node (ref "IC4") (pin "15") (pinfunction "A3_15") (pintype "input"))
      (node (ref "U$1") (pin "P$38") (pinfunction "A6_P$38") (pintype "bidirectional"))
    )
    (net (code "61") (name "Net-(IC4B-A4)") (class "Default")
      (node (ref "IC4") (pin "17") (pinfunction "A4_17") (pintype "input"))
      (node (ref "U$1") (pin "P$36") (pinfunction "A7_P$36") (pintype "bidirectional"))
    )
    (net (code "62") (name "Net-(IC5A-A1)") (class "Default")
      (node (ref "IC5") (pin "2") (pinfunction "A1_2") (pintype "input"))
      (node (ref "U$1") (pin "P$11") (pinfunction "A8_P$11") (pintype "bidirectional"))
    )
    (net (code "63") (name "Net-(IC5A-A2)") (class "Default")
      (node (ref "IC5") (pin "4") (pinfunction "A2_4") (pintype "input"))
      (node (ref "U$1") (pin "P$17") (pinfunction "A9_P$17") (pintype "bidirectional"))
    )
    (net (code "64") (name "Net-(IC5A-A3)") (class "Default")
      (node (ref "IC5") (pin "6") (pinfunction "A3_6") (pintype "input"))
      (node (ref "U$1") (pin "P$4") (pinfunction "A10_P$4") (pintype "bidirectional"))
    )
    (net (code "65") (name "Net-(IC5A-A4)") (class "Default")
      (node (ref "IC5") (pin "8") (pinfunction "A4_8") (pintype "input"))
      (node (ref "U$1") (pin "P$9") (pinfunction "A11_P$9") (pintype "bidirectional"))
    )
    (net (code "66") (name "Net-(IC5B-A1)") (class "Default")
      (node (ref "IC5") (pin "11") (pinfunction "A1_11") (pintype "input"))
      (node (ref "U$1") (pin "P$5") (pinfunction "A12_P$5") (pintype "bidirectional"))
    )
    (net (code "67") (name "Net-(IC5B-A2)") (class "Default")
      (node (ref "IC5") (pin "13") (pinfunction "A2_13") (pintype "input"))
      (node (ref "U$1") (pin "P$6") (pinfunction "A13_P$6") (pintype "bidirectional"))
    )
    (net (code "68") (name "Net-(IC5B-A3)") (class "Default")
      (node (ref "IC5") (pin "15") (pinfunction "A3_15") (pintype "input"))
      (node (ref "U$1") (pin "P$10") (pinfunction "A14_P$10") (pintype "bidirectional"))
    )
    (net (code "69") (name "Net-(IC5B-A4)") (class "Default")
      (node (ref "IC5") (pin "17") (pinfunction "A4_17") (pintype "input"))
      (node (ref "U$1") (pin "P$7") (pinfunction "A15_P$7") (pintype "bidirectional"))
    )
    (net (code "70") (name "Net-(IC5B-Y4)") (class "Default")
      (node (ref "IC5") (pin "3") (pinfunction "Y4_3") (pintype "tri_state"))
      (node (ref "IC6") (pin "4") (pinfunction "I0_4") (pintype "input"))
    )
    (net (code "71") (name "Net-(IC6A-I0)") (class "Default")
      (node (ref "IC6") (pin "1") (pinfunction "I0_1") (pintype "input"))
      (node (ref "U$1") (pin "P$1") (pinfunction "RAS*_P$1") (pintype "bidirectional"))
    )
    (net (code "72") (name "Net-(IC6A-O)") (class "Default")
      (node (ref "IC6") (pin "3") (pinfunction "O_3") (pintype "output"))
      (node (ref "IC6") (pin "5") (pinfunction "I1_5") (pintype "input"))
    )
    (net (code "73") (name "Net-(IC6C-I0)") (class "Default")
      (node (ref "IC6") (pin "9") (pinfunction "I0_9") (pintype "input"))
      (node (ref "R2") (pin "2") (pinfunction "2_2") (pintype "passive"))
      (node (ref "U11") (pin "P4") (pinfunction "READY_P4") (pintype "bidirectional"))
    )
    (net (code "74") (name "Net-(IC6C-I1)") (class "Default")
      (node (ref "IC6") (pin "10") (pinfunction "I1_10") (pintype "input"))
      (node (ref "R6") (pin "2") (pinfunction "2_2") (pintype "passive"))
      (node (ref "U4") (pin "P4") (pinfunction "READY_P4") (pintype "bidirectional"))
    )
    (net (code "75") (name "Net-(IC6C-O)") (class "Default")
      (node (ref "IC6") (pin "12") (pinfunction "I0_12") (pintype "input"))
      (node (ref "IC6") (pin "13") (pinfunction "I1_13") (pintype "input"))
      (node (ref "IC6") (pin "8") (pinfunction "O_8") (pintype "output"))
    )
    (net (code "76") (name "Net-(IC6D-O)") (class "Default")
      (node (ref "IC6") (pin "11") (pinfunction "O_11") (pintype "output"))
      (node (ref "U$1") (pin "P$33") (pinfunction "WAIT*_P$33") (pintype "bidirectional"))
    )
    (net (code "77") (name "Net-(IC8A-A1)") (class "Default")
      (node (ref "IC8") (pin "2") (pinfunction "A1_2") (pintype "input"))
      (node (ref "JOYSTICK1") (pin "2") (pinfunction "2_2") (pintype "passive"))
      (node (ref "RN1") (pin "13") (pinfunction "13_13") (pintype "passive"))
    )
    (net (code "78") (name "Net-(IC8A-A2)") (class "Default")
      (node (ref "IC8") (pin "4") (pinfunction "A2_4") (pintype "input"))
      (node (ref "JOYSTICK1") (pin "3") (pinfunction "3_3") (pintype "passive"))
      (node (ref "RN1") (pin "12") (pinfunction "12_12") (pintype "passive"))
    )
    (net (code "79") (name "Net-(IC8A-A3)") (class "Default")
      (node (ref "IC8") (pin "6") (pinfunction "A3_6") (pintype "input"))
      (node (ref "JOYSTICK1") (pin "4") (pinfunction "4_4") (pintype "passive"))
      (node (ref "RN1") (pin "11") (pinfunction "11_11") (pintype "passive"))
    )
    (net (code "80") (name "Net-(IC8A-A4)") (class "Default")
      (node (ref "IC8") (pin "8") (pinfunction "A4_8") (pintype "input"))
      (node (ref "JOYSTICK1") (pin "5") (pinfunction "5_5") (pintype "passive"))
      (node (ref "RN1") (pin "10") (pinfunction "10_10") (pintype "passive"))
    )
    (net (code "81") (name "Net-(IC8B-A1)") (class "Default")
      (node (ref "IC8") (pin "11") (pinfunction "A1_11") (pintype "input"))
      (node (ref "JOYSTICK1") (pin "9") (pinfunction "9_9") (pintype "passive"))
      (node (ref "RN1") (pin "9") (pinfunction "9_9") (pintype "passive"))
    )
    (net (code "82") (name "Net-(J4-PadPIN)") (class "Default")
      (node (ref "J4") (pin "PIN") (pinfunction "PIN_PIN") (pintype "bidirectional"))
      (node (ref "J4") (pin "SWITCH") (pinfunction "SWITCH_SWITCH") (pintype "bidirectional"))
      (node (ref "R5") (pin "2") (pinfunction "2_2") (pintype "passive"))
    )
    (net (code "83") (name "Net-(J5-PadPIN)") (class "Default")
      (node (ref "J5") (pin "PIN") (pinfunction "PIN_PIN") (pintype "bidirectional"))
      (node (ref "J5") (pin "SWITCH") (pinfunction "SWITCH_SWITCH") (pintype "bidirectional"))
      (node (ref "R1") (pin "2") (pinfunction "2_2") (pintype "passive"))
    )
    (net (code "84") (name "Net-(R8-E)") (class "Default")
      (node (ref "Q2") (pin "E") (pinfunction "E_E") (pintype "passive"))
      (node (ref "R3") (pin "1") (pinfunction "1_1") (pintype "passive"))
      (node (ref "R8") (pin "3") (pinfunction "E_3") (pintype "passive"))
    )
    (net (code "85") (name "Net-(R8-S)") (class "Default")
      (node (ref "J3") (pin "PIN") (pinfunction "PIN_PIN") (pintype "bidirectional"))
      (node (ref "J3") (pin "SWITCH") (pinfunction "SWITCH_SWITCH") (pintype "bidirectional"))
      (node (ref "R8") (pin "2") (pinfunction "S_2") (pintype "passive"))
    )
    (net (code "86") (name "Net-(REG1-VIN)") (class "Default")
      (node (ref "C5") (pin "+") (pinfunction "+_+") (pintype "passive"))
      (node (ref "REG1") (pin "P$1") (pinfunction "VIN_P$1") (pintype "bidirectional"))
      (node (ref "S1") (pin "1") (pinfunction "O_1") (pintype "passive"))
    )
    (net (code "87") (name "Net-(S1-P)") (class "Default")
      (node (ref "S1") (pin "2") (pinfunction "P_2") (pintype "passive"))
      (node (ref "U$2") (pin "3") (pinfunction "3_3") (pintype "passive"))
    )
    (net (code "88") (name "Net-(U$1-INT*)") (class "Default")
      (node (ref "JP1") (pin "1") (pinfunction "1_1") (pintype "passive"))
      (node (ref "U$1") (pin "P$21") (pinfunction "INT*_P$21") (pintype "bidirectional"))
    )
    (net (code "89") (name "Net-(U1-A0)") (class "Default")
      (node (ref "U1") (pin "14") (pinfunction "A0_14") (pintype "bidirectional"))
      (node (ref "U2") (pin "P3") (pinfunction "AD7_P3") (pintype "bidirectional"))
      (node (ref "U3") (pin "14") (pinfunction "A0_14") (pintype "bidirectional"))
    )
    (net (code "90") (name "Net-(U1-A1)") (class "Default")
      (node (ref "U1") (pin "13") (pinfunction "A1_13") (pintype "bidirectional"))
      (node (ref "U2") (pin "P4") (pinfunction "AD6_P4") (pintype "bidirectional"))
      (node (ref "U3") (pin "13") (pinfunction "A1_13") (pintype "bidirectional"))
    )
    (net (code "91") (name "Net-(U1-A2)") (class "Default")
      (node (ref "U1") (pin "12") (pinfunction "A2_12") (pintype "bidirectional"))
      (node (ref "U2") (pin "P5") (pinfunction "AD5_P5") (pintype "bidirectional"))
      (node (ref "U3") (pin "12") (pinfunction "A2_12") (pintype "bidirectional"))
    )
    (net (code "92") (name "Net-(U1-A3)") (class "Default")
      (node (ref "U1") (pin "11") (pinfunction "A3_11") (pintype "bidirectional"))
      (node (ref "U2") (pin "P6") (pinfunction "AD4_P6") (pintype "bidirectional"))
      (node (ref "U3") (pin "11") (pinfunction "A3_11") (pintype "bidirectional"))
    )
    (net (code "93") (name "Net-(U1-A4)") (class "Default")
      (node (ref "U1") (pin "8") (pinfunction "A4_8") (pintype "bidirectional"))
      (node (ref "U2") (pin "P7") (pinfunction "AD3_P7") (pintype "bidirectional"))
      (node (ref "U3") (pin "8") (pinfunction "A4_8") (pintype "bidirectional"))
    )
    (net (code "94") (name "Net-(U1-A5)") (class "Default")
      (node (ref "U1") (pin "7") (pinfunction "A5_7") (pintype "bidirectional"))
      (node (ref "U2") (pin "P8") (pinfunction "AD2_P8") (pintype "bidirectional"))
      (node (ref "U3") (pin "7") (pinfunction "A5_7") (pintype "bidirectional"))
    )
    (net (code "95") (name "Net-(U1-A6)") (class "Default")
      (node (ref "U1") (pin "6") (pinfunction "A6_6") (pintype "bidirectional"))
      (node (ref "U2") (pin "P9") (pinfunction "AD1_P9") (pintype "bidirectional"))
      (node (ref "U3") (pin "6") (pinfunction "A6_6") (pintype "bidirectional"))
    )
    (net (code "96") (name "Net-(U1-A7)") (class "Default")
      (node (ref "U1") (pin "10") (pinfunction "A7_10") (pintype "bidirectional"))
      (node (ref "U2") (pin "P10") (pinfunction "AD0_P10") (pintype "bidirectional"))
      (node (ref "U3") (pin "10") (pinfunction "A7_10") (pintype "bidirectional"))
    )
    (net (code "97") (name "Net-(U1-CAS*)") (class "Default")
      (node (ref "U1") (pin "16") (pinfunction "CAS*_16") (pintype "bidirectional"))
      (node (ref "U2") (pin "P2") (pinfunction "CAS*_P2") (pintype "bidirectional"))
      (node (ref "U3") (pin "16") (pinfunction "CAS*_16") (pintype "bidirectional"))
    )
    (net (code "98") (name "Net-(U1-DQ1)") (class "Default")
      (node (ref "U1") (pin "2") (pinfunction "DQ1_2") (pintype "bidirectional"))
      (node (ref "U2") (pin "P32") (pinfunction "RD0_P32") (pintype "bidirectional"))
    )
    (net (code "99") (name "Net-(U1-DQ2)") (class "Default")
      (node (ref "U1") (pin "3") (pinfunction "DQ2_3") (pintype "bidirectional"))
      (node (ref "U2") (pin "P31") (pinfunction "RD1_P31") (pintype "bidirectional"))
    )
    (net (code "100") (name "Net-(U1-DQ3)") (class "Default")
      (node (ref "U1") (pin "15") (pinfunction "DQ3_15") (pintype "bidirectional"))
      (node (ref "U2") (pin "P30") (pinfunction "RD2_P30") (pintype "bidirectional"))
    )
    (net (code "101") (name "Net-(U1-DQ4)") (class "Default")
      (node (ref "U1") (pin "17") (pinfunction "DQ4_17") (pintype "bidirectional"))
      (node (ref "U2") (pin "P29") (pinfunction "RD3_P29") (pintype "bidirectional"))
    )
    (net (code "102") (name "Net-(U1-RAS*)") (class "Default")
      (node (ref "U1") (pin "5") (pinfunction "RAS*_5") (pintype "bidirectional"))
      (node (ref "U2") (pin "P1") (pinfunction "RAS*_P1") (pintype "bidirectional"))
      (node (ref "U3") (pin "5") (pinfunction "RAS*_5") (pintype "bidirectional"))
    )
    (net (code "103") (name "Net-(U1-W*)") (class "Default")
      (node (ref "U1") (pin "4") (pinfunction "W*_4") (pintype "bidirectional"))
      (node (ref "U2") (pin "P11") (pinfunction "R/W*_P11") (pintype "bidirectional"))
      (node (ref "U3") (pin "4") (pinfunction "W*_4") (pintype "bidirectional"))
    )
    (net (code "104") (name "Net-(U2-COMVID)") (class "Default")
      (node (ref "Q2") (pin "B") (pinfunction "B_B") (pintype "passive"))
      (node (ref "R4") (pin "1") (pinfunction "1_1") (pintype "passive"))
      (node (ref "U2") (pin "P36") (pinfunction "COMVID_P36") (pintype "bidirectional"))
    )
    (net (code "105") (name "Net-(U2-EXTVDP)") (class "Default")
      (node (ref "J2") (pin "PIN") (pinfunction "PIN_PIN") (pintype "bidirectional"))
      (node (ref "J2") (pin "SWITCH") (pinfunction "SWITCH_SWITCH") (pintype "bidirectional"))
      (node (ref "U2") (pin "P35") (pinfunction "EXTVDP_P35") (pintype "bidirectional"))
    )
    (net (code "106") (name "Net-(U2-INT*)") (class "Default")
      (node (ref "JP1") (pin "2") (pinfunction "2_2") (pintype "passive"))
      (node (ref "U2") (pin "P16") (pinfunction "INT*_P16") (pintype "bidirectional"))
    )
    (net (code "107") (name "Net-(U2-RD4)") (class "Default")
      (node (ref "U2") (pin "P28") (pinfunction "RD4_P28") (pintype "bidirectional"))
      (node (ref "U3") (pin "2") (pinfunction "DQ1_2") (pintype "bidirectional"))
    )
    (net (code "108") (name "Net-(U2-RD5)") (class "Default")
      (node (ref "U2") (pin "P27") (pinfunction "RD5_P27") (pintype "bidirectional"))
      (node (ref "U3") (pin "3") (pinfunction "DQ2_3") (pintype "bidirectional"))
    )
    (net (code "109") (name "Net-(U2-RD6)") (class "Default")
      (node (ref "U2") (pin "P26") (pinfunction "RD6_P26") (pintype "bidirectional"))
      (node (ref "U3") (pin "15") (pinfunction "DQ3_15") (pintype "bidirectional"))
    )
    (net (code "110") (name "Net-(U2-RD7)") (class "Default")
      (node (ref "U2") (pin "P25") (pinfunction "RD7_P25") (pintype "bidirectional"))
      (node (ref "U3") (pin "17") (pinfunction "DQ4_17") (pintype "bidirectional"))
    )
    (net (code "111") (name "Net-(U4-SNDOUT)") (class "Default")
      (node (ref "C1") (pin "+") (pinfunction "+_+") (pintype "passive"))
      (node (ref "U4") (pin "P7") (pinfunction "SNDOUT_P7") (pintype "bidirectional"))
    )
    (net (code "112") (name "Net-(U11-CLOCK)") (class "Default")
      (node (ref "U11") (pin "P14") (pinfunction "CLOCK_P14") (pintype "bidirectional"))
      (node (ref "U2") (pin "P38") (pinfunction "CPUCLK_P38") (pintype "bidirectional"))
      (node (ref "U4") (pin "P14") (pinfunction "CLOCK_P14") (pintype "bidirectional"))
    )
    (net (code "113") (name "Net-(U11-SNDOUT)") (class "Default")
      (node (ref "C27") (pin "+") (pinfunction "+_+") (pintype "passive"))
      (node (ref "U11") (pin "P7") (pinfunction "SNDOUT_P7") (pintype "bidirectional"))
    )
    (net (code "114") (name "VCC") (class "Default")
      (node (ref "ATF22V10C") (pin "24") (pinfunction "VCC_24") (pintype "bidirectional"))
      (node (ref "C10") (pin "1") (pinfunction "1_1") (pintype "passive"))
      (node (ref "C12") (pin "1") (pinfunction "1_1") (pintype "passive"))
      (node (ref "C13") (pin "1") (pinfunction "1_1") (pintype "passive"))
      (node (ref "C14") (pin "1") (pinfunction "1_1") (pintype "passive"))
      (node (ref "C15") (pin "1") (pinfunction "1_1") (pintype "passive"))
      (node (ref "C16") (pin "1") (pinfunction "1_1") (pintype "passive"))
      (node (ref "C17") (pin "1") (pinfunction "1_1") (pintype "passive"))
      (node (ref "C20") (pin "1") (pinfunction "1_1") (pintype "passive"))
      (node (ref "C21") (pin "1") (pinfunction "1_1") (pintype "passive"))
      (node (ref "C4") (pin "+") (pinfunction "+_+") (pintype "passive"))
      (node (ref "C6") (pin "1") (pinfunction "1_1") (pintype "passive"))
      (node (ref "C7") (pin "1") (pinfunction "1_1") (pintype "passive"))
      (node (ref "C8") (pin "1") (pinfunction "1_1") (pintype "passive"))
      (node (ref "C9") (pin "1") (pinfunction "1_1") (pintype "passive"))
      (node (ref "IC1") (pin "20") (pinfunction "VCC_20") (pintype "power_in"))
      (node (ref "IC2") (pin "11") (pinfunction "I_11") (pintype "input"))
      (node (ref "IC2") (pin "13") (pinfunction "I_13") (pintype "input"))
      (node (ref "IC2") (pin "14") (pinfunction "VCC_14") (pintype "power_in"))
      (node (ref "IC3") (pin "28") (pinfunction "VCC_28") (pintype "power_in"))
      (node (ref "IC4") (pin "20") (pinfunction "VCC_20") (pintype "power_in"))
      (node (ref "IC5") (pin "20") (pinfunction "VCC_20") (pintype "power_in"))
      (node (ref "IC6") (pin "14") (pinfunction "VCC_14") (pintype "power_in"))
      (node (ref "IC6") (pin "2") (pinfunction "I1_2") (pintype "input"))
      (node (ref "IC8") (pin "20") (pinfunction "VCC_20") (pintype "power_in"))
      (node (ref "Q2") (pin "C") (pinfunction "C_C") (pintype "passive"))
      (node (ref "R2") (pin "1") (pinfunction "1_1") (pintype "passive"))
      (node (ref "R6") (pin "1") (pinfunction "1_1") (pintype "passive"))
      (node (ref "R7") (pin "1") (pinfunction "1_1") (pintype "passive"))
      (node (ref "R9") (pin "2") (pinfunction "2_2") (pintype "passive"))
      (node (ref "REG1") (pin "P$3") (pinfunction "VOUT_P$3") (pintype "bidirectional"))
      (node (ref "RN1") (pin "1") (pinfunction "1_1") (pintype "passive"))
      (node (ref "U1") (pin "9") (pinfunction "VDD_9") (pintype "bidirectional"))
      (node (ref "U11") (pin "P16") (pinfunction "VCC_P16") (pintype "bidirectional"))
      (node (ref "U2") (pin "P33") (pinfunction "VDD_P33") (pintype "bidirectional"))
      (node (ref "U3") (pin "9") (pinfunction "VDD_9") (pintype "bidirectional"))
      (node (ref "U4") (pin "P16") (pinfunction "VCC_P16") (pintype "bidirectional"))
    )
    (net (code "115") (name "unconnected-(ATF22V10C-NC-Pad1)") (class "Default")
      (node (ref "ATF22V10C") (pin "1") (pinfunction "NC_1") (pintype "bidirectional"))
    )
    (net (code "116") (name "unconnected-(ATF22V10C-NC2-Pad4)") (class "Default")
      (node (ref "ATF22V10C") (pin "4") (pinfunction "NC2_4") (pintype "bidirectional"))
    )
    (net (code "117") (name "unconnected-(ATF22V10C-NC5-Pad23)") (class "Default")
      (node (ref "ATF22V10C") (pin "23") (pinfunction "NC5_23") (pintype "bidirectional"))
    )
    (net (code "118") (name "unconnected-(IC2E-O-Pad10)") (class "Default")
      (node (ref "IC2") (pin "10") (pinfunction "O_10") (pintype "output"))
    )
    (net (code "119") (name "unconnected-(IC2F-O-Pad12)") (class "Default")
      (node (ref "IC2") (pin "12") (pinfunction "O_12") (pintype "output"))
    )
    (net (code "120") (name "unconnected-(JOYSTICK1-Pad1)") (class "Default")
      (node (ref "JOYSTICK1") (pin "1") (pinfunction "1_1") (pintype "passive"))
    )
    (net (code "121") (name "unconnected-(JOYSTICK1-Pad6)") (class "Default")
      (node (ref "JOYSTICK1") (pin "6") (pinfunction "6_6") (pintype "passive"))
    )
    (net (code "122") (name "unconnected-(JOYSTICK1-Pad8)") (class "Default")
      (node (ref "JOYSTICK1") (pin "8") (pinfunction "8_8") (pintype "passive"))
    )
    (net (code "123") (name "unconnected-(JOYSTICK2-Pad1)") (class "Default")
      (node (ref "JOYSTICK2") (pin "1") (pinfunction "1_1") (pintype "passive"))
    )
    (net (code "124") (name "unconnected-(JOYSTICK2-Pad6)") (class "Default")
      (node (ref "JOYSTICK2") (pin "6") (pinfunction "6_6") (pintype "passive"))
    )
    (net (code "125") (name "unconnected-(JOYSTICK2-Pad8)") (class "Default")
      (node (ref "JOYSTICK2") (pin "8") (pinfunction "8_8") (pintype "passive"))
    )
    (net (code "126") (name "unconnected-(R8-A-Pad1)") (class "Default")
      (node (ref "R8") (pin "1") (pinfunction "A_1") (pintype "passive"))
    )
    (net (code "127") (name "unconnected-(RN1-Pad2)") (class "Default")
      (node (ref "RN1") (pin "2") (pinfunction "2_2") (pintype "passive"))
    )
    (net (code "128") (name "unconnected-(S1-S-Pad3)") (class "Default")
      (node (ref "S1") (pin "3") (pinfunction "S_3") (pintype "passive"))
    )
    (net (code "129") (name "unconnected-(U$1-CAS*-PadP$3)") (class "Default")
      (node (ref "U$1") (pin "P$3") (pinfunction "CAS*_P$3") (pintype "bidirectional"))
    )
    (net (code "130") (name "unconnected-(U$1-GND3-PadP$37)") (class "Default")
      (node (ref "U$1") (pin "P$37") (pinfunction "GND3_P$37") (pintype "bidirectional"))
    )
    (net (code "131") (name "unconnected-(U$1-INTAK*-PadP$14)") (class "Default")
      (node (ref "U$1") (pin "P$14") (pinfunction "INTAK*_P$14") (pintype "bidirectional"))
    )
    (net (code "132") (name "unconnected-(U$1-MUX-PadP$16)") (class "Default")
      (node (ref "U$1") (pin "P$16") (pinfunction "MUX_P$16") (pintype "bidirectional"))
    )
    (net (code "133") (name "unconnected-(U$1-NC-PadP$39)") (class "Default")
      (node (ref "U$1") (pin "P$39") (pinfunction "NC_P$39") (pintype "bidirectional"))
    )
    (net (code "134") (name "unconnected-(U$1-TEST*-PadP$23)") (class "Default")
      (node (ref "U$1") (pin "P$23") (pinfunction "TEST*_P$23") (pintype "bidirectional"))
    )
    (net (code "135") (name "unconnected-(U2-NC-PadP37)") (class "Default")
      (node (ref "U2") (pin "P37") (pinfunction "NC_P37") (pintype "bidirectional"))
    )
    (net (code "136") (name "unconnected-(U4-NC-PadP9)") (class "Default")
      (node (ref "U4") (pin "P9") (pinfunction "NC_P9") (pintype "bidirectional"))
    )
    (net (code "137") (name "unconnected-(U11-NC-PadP9)") (class "Default")
      (node (ref "U11") (pin "P9") (pinfunction "NC_P9") (pintype "bidirectional"))
    )
  )
)
